# alarmclock4.net
KiCad netlist of a schematic drawn in EAGLE
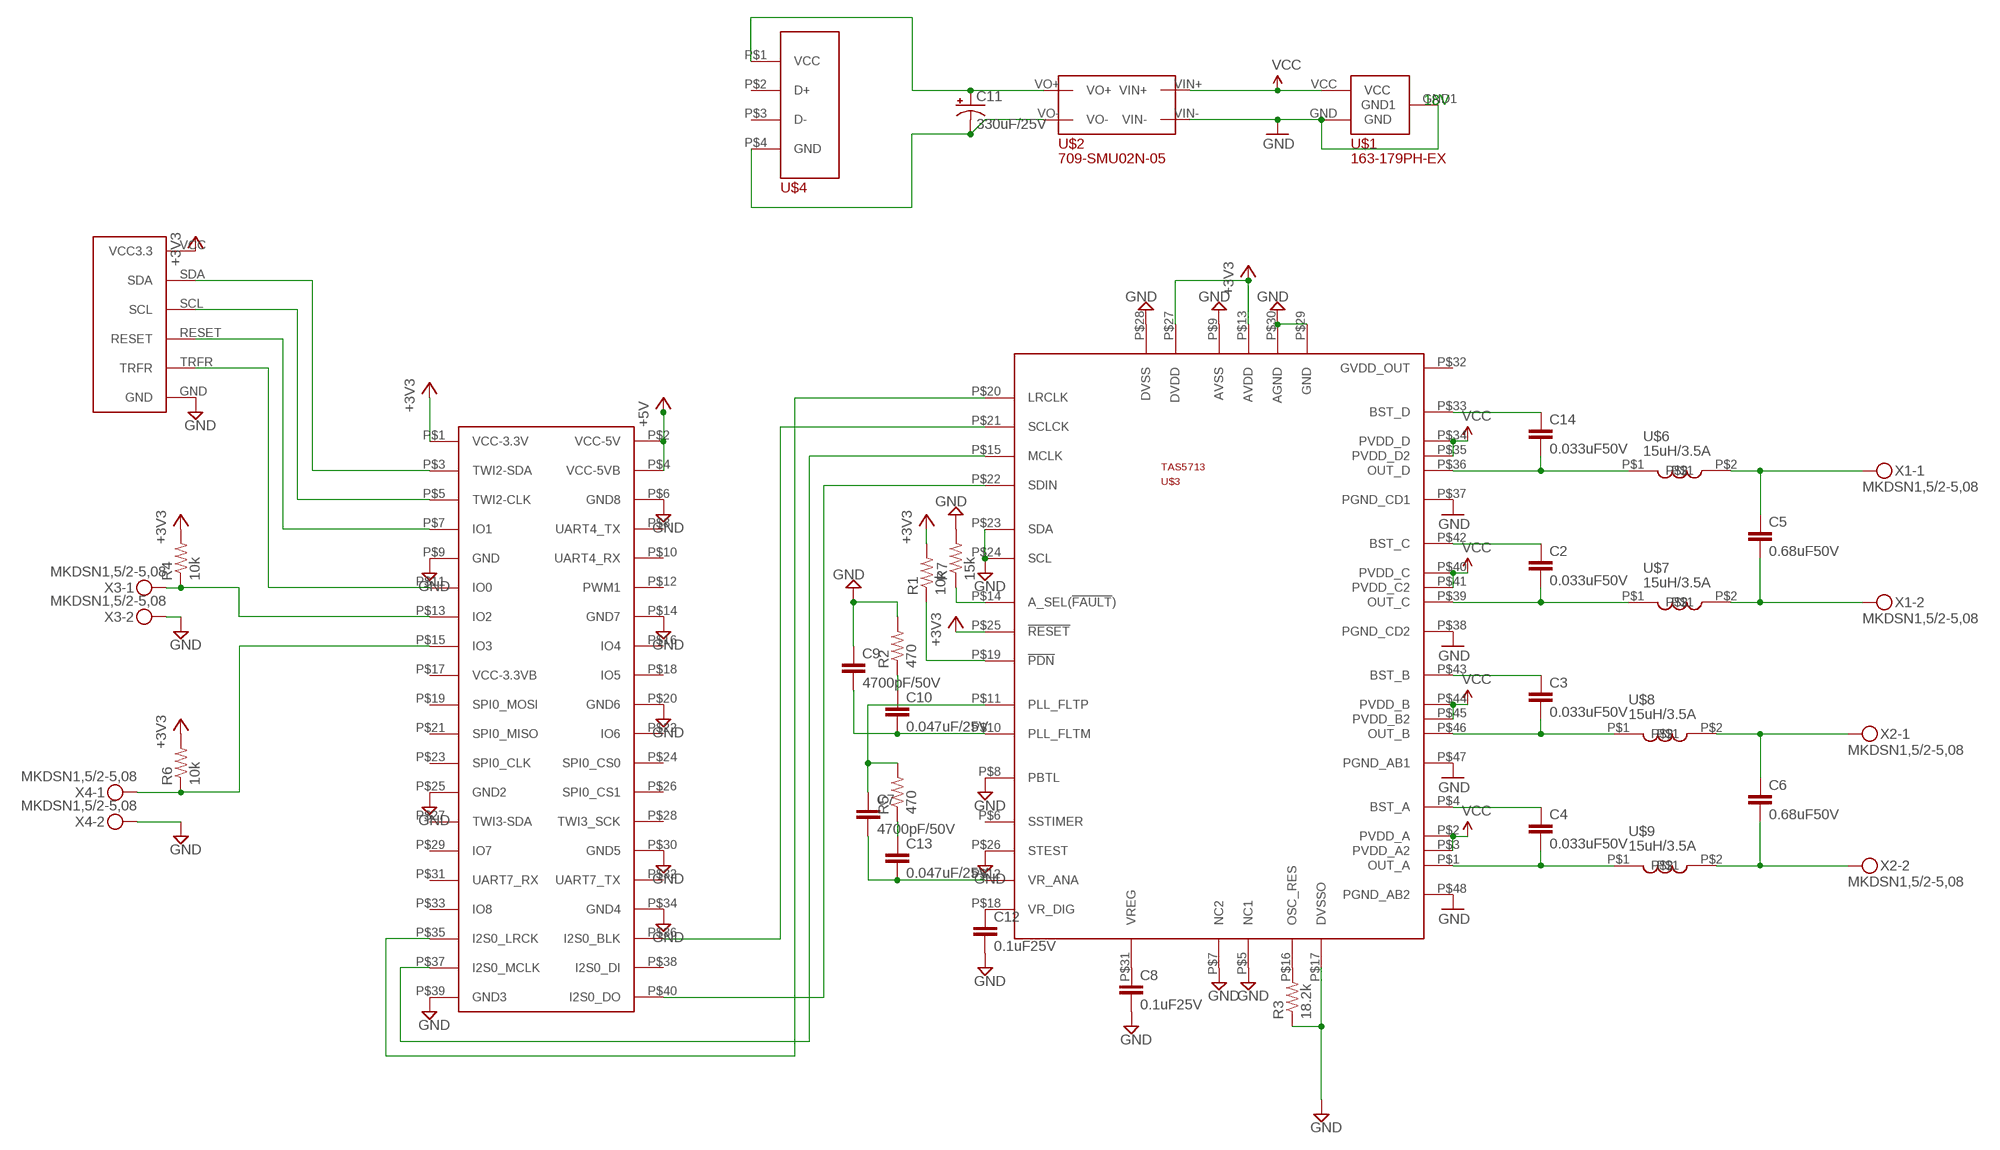
[diagram p0: schematic, sheet 1]

(export (version "E")
  (design (tool "Eeschema 10.0.6"))
  (components
    (comp (ref "C2")
      (value "0.033uF50V")
      (footprint "eagle-import:0603-CAP")
      (libsource (lib "eagle-import") (part "CAP0603-CAP"))
    )
    (comp (ref "C3")
      (value "0.033uF50V")
      (footprint "eagle-import:0603-CAP")
      (libsource (lib "eagle-import") (part "CAP0603-CAP"))
    )
    (comp (ref "C4")
      (value "0.033uF50V")
      (footprint "eagle-import:0603-CAP")
      (libsource (lib "eagle-import") (part "CAP0603-CAP"))
    )
    (comp (ref "C5")
      (value "0.68uF50V")
      (footprint "eagle-import:0603-CAP")
      (libsource (lib "eagle-import") (part "CAP0603-CAP"))
    )
    (comp (ref "C6")
      (value "0.68uF50V")
      (footprint "eagle-import:0603-CAP")
      (libsource (lib "eagle-import") (part "CAP0603-CAP"))
    )
    (comp (ref "C7")
      (value "4700pF/50V")
      (footprint "eagle-import:0603-CAP")
      (libsource (lib "eagle-import") (part "CAP0603-CAP"))
    )
    (comp (ref "C8")
      (value "0.1uF25V")
      (footprint "eagle-import:0603-CAP")
      (libsource (lib "eagle-import") (part "CAP0603-CAP"))
    )
    (comp (ref "C9")
      (value "4700pF/50V")
      (footprint "eagle-import:0603-CAP")
      (libsource (lib "eagle-import") (part "CAP0603-CAP"))
    )
    (comp (ref "C10")
      (value "0.047uF/25V")
      (footprint "eagle-import:0603-CAP")
      (libsource (lib "eagle-import") (part "CAP0603-CAP"))
    )
    (comp (ref "C11")
      (value "330uF/25V")
      (footprint "eagle-import:CPOL-RADIAL-10UF-25V")
      (libsource (lib "eagle-import") (part "CAP_POLPTH2"))
    )
    (comp (ref "C12")
      (value "0.1uF25V")
      (footprint "eagle-import:0603-CAP")
      (libsource (lib "eagle-import") (part "CAP0603-CAP"))
    )
    (comp (ref "C13")
      (value "0.047uF/25V")
      (footprint "eagle-import:0603-CAP")
      (libsource (lib "eagle-import") (part "CAP0603-CAP"))
    )
    (comp (ref "C14")
      (value "0.033uF50V")
      (footprint "eagle-import:0603-CAP")
      (libsource (lib "eagle-import") (part "CAP0603-CAP"))
    )
    (comp (ref "R1")
      (value "10k")
      (footprint "eagle-import:0603-RES")
      (libsource (lib "eagle-import") (part "RESISTOR0603-RES"))
    )
    (comp (ref "R2")
      (value "470")
      (footprint "eagle-import:0603-RES")
      (libsource (lib "eagle-import") (part "RESISTOR0603-RES"))
    )
    (comp (ref "R3")
      (value "18.2k")
      (footprint "eagle-import:0603-RES")
      (libsource (lib "eagle-import") (part "RESISTOR0603-RES"))
    )
    (comp (ref "R4")
      (value "10k")
      (footprint "eagle-import:0603-RES")
      (libsource (lib "eagle-import") (part "RESISTOR0603-RES"))
    )
    (comp (ref "R5")
      (value "470")
      (footprint "eagle-import:0603-RES")
      (libsource (lib "eagle-import") (part "RESISTOR0603-RES"))
    )
    (comp (ref "R6")
      (value "10k")
      (footprint "eagle-import:0603-RES")
      (libsource (lib "eagle-import") (part "RESISTOR0603-RES"))
    )
    (comp (ref "R7")
      (value "15k")
      (footprint "eagle-import:0603-RES")
      (libsource (lib "eagle-import") (part "RESISTOR0603-RES"))
    )
    (comp (ref "U$1")
      (value "163-179PH-EX")
      (footprint "eagle-import:163-179PH-EX_DIM")
      (libsource (lib "eagle-import") (part "163-179PH-EX"))
    )
    (comp (ref "U$2")
      (value "709-SMU02N-05")
      (footprint "eagle-import:709-SMU02N-05_DIM")
      (libsource (lib "eagle-import") (part "709-SMU02N-05"))
    )
    (comp (ref "U$3")
      (value "TAS5713")
      (footprint "eagle-import:TAS5713_DIM")
      (libsource (lib "eagle-import") (part "TAS5713"))
    )
    (comp (ref "U$4")
      (value "USB_TYPEA_CONNECTOR")
      (footprint "eagle-import:USB_DIM")
      (libsource (lib "eagle-import") (part "USB_TYPEA_CONNECTOR"))
    )
    (comp (ref "U$5")
      (value "BANANAPRO-CON6")
      (footprint "eagle-import:BANANAPRO-CON6_DIM")
      (libsource (lib "eagle-import") (part "BANANAPRO-CON6"))
    )
    (comp (ref "U$6")
      (value "15uH/3.5A")
      (footprint "eagle-import:MSS1260_DIM")
      (libsource (lib "eagle-import") (part "MSS1260INDUCTOR"))
    )
    (comp (ref "U$7")
      (value "15uH/3.5A")
      (footprint "eagle-import:MSS1260_DIM")
      (libsource (lib "eagle-import") (part "MSS1260INDUCTOR"))
    )
    (comp (ref "U$8")
      (value "15uH/3.5A")
      (footprint "eagle-import:MSS1260_DIM")
      (libsource (lib "eagle-import") (part "MSS1260INDUCTOR"))
    )
    (comp (ref "U$9")
      (value "15uH/3.5A")
      (footprint "eagle-import:MSS1260_DIM")
      (libsource (lib "eagle-import") (part "MSS1260INDUCTOR"))
    )
    (comp (ref "U$10")
      (value "SKYWRITER")
      (footprint "eagle-import:SKYWRITER_DIM")
      (libsource (lib "eagle-import") (part "SKYWRITER"))
    )
    (comp (ref "X1")
      (value "MKDSN1,5/2-5,08")
      (footprint "eagle-import:MKDSN1,5_2-5,08")
      (libsource (lib "eagle-import") (part "MKDSN1,5/2-5,08"))
    )
    (comp (ref "X2")
      (value "MKDSN1,5/2-5,08")
      (footprint "eagle-import:MKDSN1,5_2-5,08")
      (libsource (lib "eagle-import") (part "MKDSN1,5/2-5,08"))
    )
    (comp (ref "X3")
      (value "MKDSN1,5/2-5,08")
      (footprint "eagle-import:MKDSN1,5_2-5,08")
      (libsource (lib "eagle-import") (part "MKDSN1,5/2-5,08"))
    )
    (comp (ref "X4")
      (value "MKDSN1,5/2-5,08")
      (footprint "eagle-import:MKDSN1,5_2-5,08")
      (libsource (lib "eagle-import") (part "MKDSN1,5/2-5,08"))
    )
  )
  (nets
    (net (code "1") (name "+3V3") (class "Default")
      (node (ref "R1") (pin "2") (pinfunction "2_2") (pintype "passive"))
      (node (ref "R4") (pin "2") (pinfunction "2_2") (pintype "passive"))
      (node (ref "R6") (pin "2") (pinfunction "2_2") (pintype "passive"))
      (node (ref "U$10") (pin "VCC") (pinfunction "VCC3.3_VCC") (pintype "bidirectional"))
      (node (ref "U$3") (pin "P$13") (pinfunction "AVDD_P$13") (pintype "bidirectional"))
      (node (ref "U$3") (pin "P$25") (pinfunction "~{RESET}_P$25") (pintype "bidirectional"))
      (node (ref "U$3") (pin "P$27") (pinfunction "DVDD_P$27") (pintype "bidirectional"))
      (node (ref "U$5") (pin "P$1") (pinfunction "VCC-3.3V_P$1") (pintype "bidirectional"))
    )
    (net (code "2") (name "+5V") (class "Default")
      (node (ref "U$5") (pin "P$2") (pinfunction "VCC-5V_P$2") (pintype "bidirectional"))
      (node (ref "U$5") (pin "P$4") (pinfunction "VCC-5VB_P$4") (pintype "bidirectional"))
    )
    (net (code "3") (name "GND") (class "Default")
      (node (ref "C12") (pin "2") (pinfunction "2_2") (pintype "passive"))
      (node (ref "C8") (pin "2") (pinfunction "2_2") (pintype "passive"))
      (node (ref "C9") (pin "1") (pinfunction "1_1") (pintype "passive"))
      (node (ref "R2") (pin "2") (pinfunction "2_2") (pintype "passive"))
      (node (ref "R3") (pin "1") (pinfunction "1_1") (pintype "passive"))
      (node (ref "R7") (pin "2") (pinfunction "2_2") (pintype "passive"))
      (node (ref "U$1") (pin "GND") (pinfunction "GND_GND") (pintype "bidirectional"))
      (node (ref "U$1") (pin "GND1") (pinfunction "GND1_GND1") (pintype "bidirectional"))
      (node (ref "U$10") (pin "GND") (pinfunction "GND_GND") (pintype "bidirectional"))
      (node (ref "U$2") (pin "VIN-") (pinfunction "VIN-_VIN-") (pintype "bidirectional"))
      (node (ref "U$3") (pin "P$17") (pinfunction "DVSSO_P$17") (pintype "bidirectional"))
      (node (ref "U$3") (pin "P$23") (pinfunction "SDA_P$23") (pintype "bidirectional"))
      (node (ref "U$3") (pin "P$24") (pinfunction "SCL_P$24") (pintype "bidirectional"))
      (node (ref "U$3") (pin "P$26") (pinfunction "STEST_P$26") (pintype "bidirectional"))
      (node (ref "U$3") (pin "P$28") (pinfunction "DVSS_P$28") (pintype "bidirectional"))
      (node (ref "U$3") (pin "P$29") (pinfunction "GND_P$29") (pintype "bidirectional"))
      (node (ref "U$3") (pin "P$30") (pinfunction "AGND_P$30") (pintype "bidirectional"))
      (node (ref "U$3") (pin "P$37") (pinfunction "PGND_CD1_P$37") (pintype "bidirectional"))
      (node (ref "U$3") (pin "P$38") (pinfunction "PGND_CD2_P$38") (pintype "bidirectional"))
      (node (ref "U$3") (pin "P$47") (pinfunction "PGND_AB1_P$47") (pintype "bidirectional"))
      (node (ref "U$3") (pin "P$48") (pinfunction "PGND_AB2_P$48") (pintype "bidirectional"))
      (node (ref "U$3") (pin "P$5") (pinfunction "NC1_P$5") (pintype "bidirectional"))
      (node (ref "U$3") (pin "P$7") (pinfunction "NC2_P$7") (pintype "bidirectional"))
      (node (ref "U$3") (pin "P$8") (pinfunction "PBTL_P$8") (pintype "bidirectional"))
      (node (ref "U$3") (pin "P$9") (pinfunction "AVSS_P$9") (pintype "bidirectional"))
      (node (ref "U$5") (pin "P$14") (pinfunction "GND7_P$14") (pintype "bidirectional"))
      (node (ref "U$5") (pin "P$20") (pinfunction "GND6_P$20") (pintype "bidirectional"))
      (node (ref "U$5") (pin "P$25") (pinfunction "GND2_P$25") (pintype "bidirectional"))
      (node (ref "U$5") (pin "P$30") (pinfunction "GND5_P$30") (pintype "bidirectional"))
      (node (ref "U$5") (pin "P$34") (pinfunction "GND4_P$34") (pintype "bidirectional"))
      (node (ref "U$5") (pin "P$39") (pinfunction "GND3_P$39") (pintype "bidirectional"))
      (node (ref "U$5") (pin "P$6") (pinfunction "GND8_P$6") (pintype "bidirectional"))
      (node (ref "U$5") (pin "P$9") (pinfunction "GND_P$9") (pintype "bidirectional"))
      (node (ref "X3") (pin "2") (pinfunction "KL_2") (pintype "passive"))
      (node (ref "X4") (pin "2") (pinfunction "KL_2") (pintype "passive"))
    )
    (net (code "4") (name "Net-(C10-Pad1)") (class "Default")
      (node (ref "C10") (pin "1") (pinfunction "1_1") (pintype "passive"))
      (node (ref "R2") (pin "1") (pinfunction "1_1") (pintype "passive"))
    )
    (net (code "5") (name "Net-(C11-+)") (class "Default")
      (node (ref "C11") (pin "1") (pinfunction "+_1") (pintype "passive"))
      (node (ref "U$2") (pin "VO+") (pinfunction "VO+_VO+") (pintype "bidirectional"))
      (node (ref "U$4") (pin "P$1") (pinfunction "VCC_P$1") (pintype "bidirectional"))
    )
    (net (code "6") (name "Net-(C11--)") (class "Default")
      (node (ref "C11") (pin "2") (pinfunction "-_2") (pintype "passive"))
      (node (ref "U$2") (pin "VO-") (pinfunction "VO-_VO-") (pintype "bidirectional"))
      (node (ref "U$4") (pin "P$4") (pinfunction "GND_P$4") (pintype "bidirectional"))
    )
    (net (code "7") (name "Net-(C13-Pad1)") (class "Default")
      (node (ref "C13") (pin "1") (pinfunction "1_1") (pintype "passive"))
      (node (ref "R5") (pin "1") (pinfunction "1_1") (pintype "passive"))
    )
    (net (code "8") (name "Net-(U$3-A_SEL(~{FAULT}))") (class "Default")
      (node (ref "R7") (pin "1") (pinfunction "1_1") (pintype "passive"))
      (node (ref "U$3") (pin "P$14") (pinfunction "A_SEL(~{FAULT})_P$14") (pintype "bidirectional"))
    )
    (net (code "9") (name "Net-(U$3-BST_A)") (class "Default")
      (node (ref "C4") (pin "1") (pinfunction "1_1") (pintype "passive"))
      (node (ref "U$3") (pin "P$4") (pinfunction "BST_A_P$4") (pintype "bidirectional"))
    )
    (net (code "10") (name "Net-(U$3-BST_B)") (class "Default")
      (node (ref "C3") (pin "1") (pinfunction "1_1") (pintype "passive"))
      (node (ref "U$3") (pin "P$43") (pinfunction "BST_B_P$43") (pintype "bidirectional"))
    )
    (net (code "11") (name "Net-(U$3-BST_C)") (class "Default")
      (node (ref "C2") (pin "1") (pinfunction "1_1") (pintype "passive"))
      (node (ref "U$3") (pin "P$42") (pinfunction "BST_C_P$42") (pintype "bidirectional"))
    )
    (net (code "12") (name "Net-(U$3-BST_D)") (class "Default")
      (node (ref "C14") (pin "1") (pinfunction "1_1") (pintype "passive"))
      (node (ref "U$3") (pin "P$33") (pinfunction "BST_D_P$33") (pintype "bidirectional"))
    )
    (net (code "13") (name "Net-(U$3-LRCLK)") (class "Default")
      (node (ref "U$3") (pin "P$20") (pinfunction "LRCLK_P$20") (pintype "bidirectional"))
      (node (ref "U$5") (pin "P$35") (pinfunction "I2S0_LRCK_P$35") (pintype "bidirectional"))
    )
    (net (code "14") (name "Net-(U$3-MCLK)") (class "Default")
      (node (ref "U$3") (pin "P$15") (pinfunction "MCLK_P$15") (pintype "bidirectional"))
      (node (ref "U$5") (pin "P$37") (pinfunction "I2S0_MCLK_P$37") (pintype "bidirectional"))
    )
    (net (code "15") (name "Net-(U$3-OSC_RES)") (class "Default")
      (node (ref "R3") (pin "2") (pinfunction "2_2") (pintype "passive"))
      (node (ref "U$3") (pin "P$16") (pinfunction "OSC_RES_P$16") (pintype "bidirectional"))
    )
    (net (code "16") (name "Net-(U$3-OUT_A)") (class "Default")
      (node (ref "C4") (pin "2") (pinfunction "2_2") (pintype "passive"))
      (node (ref "U$3") (pin "P$1") (pinfunction "OUT_A_P$1") (pintype "bidirectional"))
      (node (ref "U$9") (pin "P$1") (pinfunction "P$1_P$1") (pintype "bidirectional"))
    )
    (net (code "17") (name "Net-(U$3-OUT_B)") (class "Default")
      (node (ref "C3") (pin "2") (pinfunction "2_2") (pintype "passive"))
      (node (ref "U$3") (pin "P$46") (pinfunction "OUT_B_P$46") (pintype "bidirectional"))
      (node (ref "U$8") (pin "P$1") (pinfunction "P$1_P$1") (pintype "bidirectional"))
    )
    (net (code "18") (name "Net-(U$3-OUT_C)") (class "Default")
      (node (ref "C2") (pin "2") (pinfunction "2_2") (pintype "passive"))
      (node (ref "U$3") (pin "P$39") (pinfunction "OUT_C_P$39") (pintype "bidirectional"))
      (node (ref "U$7") (pin "P$1") (pinfunction "P$1_P$1") (pintype "bidirectional"))
    )
    (net (code "19") (name "Net-(U$3-OUT_D)") (class "Default")
      (node (ref "C14") (pin "2") (pinfunction "2_2") (pintype "passive"))
      (node (ref "U$3") (pin "P$36") (pinfunction "OUT_D_P$36") (pintype "bidirectional"))
      (node (ref "U$6") (pin "P$1") (pinfunction "P$1_P$1") (pintype "bidirectional"))
    )
    (net (code "20") (name "Net-(U$3-PLL_FLTM)") (class "Default")
      (node (ref "C10") (pin "2") (pinfunction "2_2") (pintype "passive"))
      (node (ref "C9") (pin "2") (pinfunction "2_2") (pintype "passive"))
      (node (ref "U$3") (pin "P$10") (pinfunction "PLL_FLTM_P$10") (pintype "bidirectional"))
    )
    (net (code "21") (name "Net-(U$3-PLL_FLTP)") (class "Default")
      (node (ref "C7") (pin "1") (pinfunction "1_1") (pintype "passive"))
      (node (ref "R5") (pin "2") (pinfunction "2_2") (pintype "passive"))
      (node (ref "U$3") (pin "P$11") (pinfunction "PLL_FLTP_P$11") (pintype "bidirectional"))
    )
    (net (code "22") (name "Net-(U$3-SCLCK)") (class "Default")
      (node (ref "U$3") (pin "P$21") (pinfunction "SCLCK_P$21") (pintype "bidirectional"))
      (node (ref "U$5") (pin "P$36") (pinfunction "I2S0_BLK_P$36") (pintype "bidirectional"))
    )
    (net (code "23") (name "Net-(U$3-SDIN)") (class "Default")
      (node (ref "U$3") (pin "P$22") (pinfunction "SDIN_P$22") (pintype "bidirectional"))
      (node (ref "U$5") (pin "P$40") (pinfunction "I2S0_DO_P$40") (pintype "bidirectional"))
    )
    (net (code "24") (name "Net-(U$3-VREG)") (class "Default")
      (node (ref "C8") (pin "1") (pinfunction "1_1") (pintype "passive"))
      (node (ref "U$3") (pin "P$31") (pinfunction "VREG_P$31") (pintype "bidirectional"))
    )
    (net (code "25") (name "Net-(U$3-VR_ANA)") (class "Default")
      (node (ref "C13") (pin "2") (pinfunction "2_2") (pintype "passive"))
      (node (ref "C7") (pin "2") (pinfunction "2_2") (pintype "passive"))
      (node (ref "U$3") (pin "P$12") (pinfunction "VR_ANA_P$12") (pintype "bidirectional"))
    )
    (net (code "26") (name "Net-(U$3-VR_DIG)") (class "Default")
      (node (ref "C12") (pin "1") (pinfunction "1_1") (pintype "passive"))
      (node (ref "U$3") (pin "P$18") (pinfunction "VR_DIG_P$18") (pintype "bidirectional"))
    )
    (net (code "27") (name "Net-(U$3-~{PDN})") (class "Default")
      (node (ref "R1") (pin "1") (pinfunction "1_1") (pintype "passive"))
      (node (ref "U$3") (pin "P$19") (pinfunction "~{PDN}_P$19") (pintype "bidirectional"))
    )
    (net (code "28") (name "Net-(U$5-IO0)") (class "Default")
      (node (ref "U$10") (pin "TRFR") (pinfunction "TRFR_TRFR") (pintype "bidirectional"))
      (node (ref "U$5") (pin "P$11") (pinfunction "IO0_P$11") (pintype "bidirectional"))
    )
    (net (code "29") (name "Net-(U$5-IO1)") (class "Default")
      (node (ref "U$10") (pin "RESET") (pinfunction "RESET_RESET") (pintype "bidirectional"))
      (node (ref "U$5") (pin "P$7") (pinfunction "IO1_P$7") (pintype "bidirectional"))
    )
    (net (code "30") (name "Net-(U$5-IO2)") (class "Default")
      (node (ref "R4") (pin "1") (pinfunction "1_1") (pintype "passive"))
      (node (ref "U$5") (pin "P$13") (pinfunction "IO2_P$13") (pintype "bidirectional"))
      (node (ref "X3") (pin "1") (pinfunction "KL_1") (pintype "passive"))
    )
    (net (code "31") (name "Net-(U$5-IO3)") (class "Default")
      (node (ref "R6") (pin "1") (pinfunction "1_1") (pintype "passive"))
      (node (ref "U$5") (pin "P$15") (pinfunction "IO3_P$15") (pintype "bidirectional"))
      (node (ref "X4") (pin "1") (pinfunction "KL_1") (pintype "passive"))
    )
    (net (code "32") (name "Net-(U$5-TWI2-CLK)") (class "Default")
      (node (ref "U$10") (pin "SCL") (pinfunction "SCL_SCL") (pintype "bidirectional"))
      (node (ref "U$5") (pin "P$5") (pinfunction "TWI2-CLK_P$5") (pintype "bidirectional"))
    )
    (net (code "33") (name "Net-(U$5-TWI2-SDA)") (class "Default")
      (node (ref "U$10") (pin "SDA") (pinfunction "SDA_SDA") (pintype "bidirectional"))
      (node (ref "U$5") (pin "P$3") (pinfunction "TWI2-SDA_P$3") (pintype "bidirectional"))
    )
    (net (code "34") (name "Net-(X1A-KL)") (class "Default")
      (node (ref "C5") (pin "1") (pinfunction "1_1") (pintype "passive"))
      (node (ref "U$6") (pin "P$2") (pinfunction "P$2_P$2") (pintype "bidirectional"))
      (node (ref "X1") (pin "1") (pinfunction "KL_1") (pintype "passive"))
    )
    (net (code "35") (name "Net-(X1B-KL)") (class "Default")
      (node (ref "C5") (pin "2") (pinfunction "2_2") (pintype "passive"))
      (node (ref "U$7") (pin "P$2") (pinfunction "P$2_P$2") (pintype "bidirectional"))
      (node (ref "X1") (pin "2") (pinfunction "KL_2") (pintype "passive"))
    )
    (net (code "36") (name "Net-(X2A-KL)") (class "Default")
      (node (ref "C6") (pin "1") (pinfunction "1_1") (pintype "passive"))
      (node (ref "U$8") (pin "P$2") (pinfunction "P$2_P$2") (pintype "bidirectional"))
      (node (ref "X2") (pin "1") (pinfunction "KL_1") (pintype "passive"))
    )
    (net (code "37") (name "Net-(X2B-KL)") (class "Default")
      (node (ref "C6") (pin "2") (pinfunction "2_2") (pintype "passive"))
      (node (ref "U$9") (pin "P$2") (pinfunction "P$2_P$2") (pintype "bidirectional"))
      (node (ref "X2") (pin "2") (pinfunction "KL_2") (pintype "passive"))
    )
    (net (code "38") (name "VCC") (class "Default")
      (node (ref "U$1") (pin "VCC") (pinfunction "VCC_VCC") (pintype "bidirectional"))
      (node (ref "U$2") (pin "VIN+") (pinfunction "VIN+_VIN+") (pintype "bidirectional"))
      (node (ref "U$3") (pin "P$2") (pinfunction "PVDD_A_P$2") (pintype "bidirectional"))
      (node (ref "U$3") (pin "P$3") (pinfunction "PVDD_A2_P$3") (pintype "bidirectional"))
      (node (ref "U$3") (pin "P$34") (pinfunction "PVDD_D_P$34") (pintype "bidirectional"))
      (node (ref "U$3") (pin "P$35") (pinfunction "PVDD_D2_P$35") (pintype "bidirectional"))
      (node (ref "U$3") (pin "P$40") (pinfunction "PVDD_C_P$40") (pintype "bidirectional"))
      (node (ref "U$3") (pin "P$41") (pinfunction "PVDD_C2_P$41") (pintype "bidirectional"))
      (node (ref "U$3") (pin "P$44") (pinfunction "PVDD_B_P$44") (pintype "bidirectional"))
      (node (ref "U$3") (pin "P$45") (pinfunction "PVDD_B2_P$45") (pintype "bidirectional"))
    )
    (net (code "39") (name "unconnected-(U$3-GVDD_OUT-PadP$32)") (class "Default")
      (node (ref "U$3") (pin "P$32") (pinfunction "GVDD_OUT_P$32") (pintype "bidirectional"))
    )
    (net (code "40") (name "unconnected-(U$3-SSTIMER-PadP$6)") (class "Default")
      (node (ref "U$3") (pin "P$6") (pinfunction "SSTIMER_P$6") (pintype "bidirectional"))
    )
    (net (code "41") (name "unconnected-(U$4-D+-PadP$2)") (class "Default")
      (node (ref "U$4") (pin "P$2") (pinfunction "D+_P$2") (pintype "bidirectional"))
    )
    (net (code "42") (name "unconnected-(U$4-D--PadP$3)") (class "Default")
      (node (ref "U$4") (pin "P$3") (pinfunction "D-_P$3") (pintype "bidirectional"))
    )
    (net (code "43") (name "unconnected-(U$5-I2S0_DI-PadP$38)") (class "Default")
      (node (ref "U$5") (pin "P$38") (pinfunction "I2S0_DI_P$38") (pintype "bidirectional"))
    )
    (net (code "44") (name "unconnected-(U$5-IO4-PadP$16)") (class "Default")
      (node (ref "U$5") (pin "P$16") (pinfunction "IO4_P$16") (pintype "bidirectional"))
    )
    (net (code "45") (name "unconnected-(U$5-IO5-PadP$18)") (class "Default")
      (node (ref "U$5") (pin "P$18") (pinfunction "IO5_P$18") (pintype "bidirectional"))
    )
    (net (code "46") (name "unconnected-(U$5-IO6-PadP$22)") (class "Default")
      (node (ref "U$5") (pin "P$22") (pinfunction "IO6_P$22") (pintype "bidirectional"))
    )
    (net (code "47") (name "unconnected-(U$5-IO7-PadP$29)") (class "Default")
      (node (ref "U$5") (pin "P$29") (pinfunction "IO7_P$29") (pintype "bidirectional"))
    )
    (net (code "48") (name "unconnected-(U$5-IO8-PadP$33)") (class "Default")
      (node (ref "U$5") (pin "P$33") (pinfunction "IO8_P$33") (pintype "bidirectional"))
    )
    (net (code "49") (name "unconnected-(U$5-PWM1-PadP$12)") (class "Default")
      (node (ref "U$5") (pin "P$12") (pinfunction "PWM1_P$12") (pintype "bidirectional"))
    )
    (net (code "50") (name "unconnected-(U$5-SPI0_CLK-PadP$23)") (class "Default")
      (node (ref "U$5") (pin "P$23") (pinfunction "SPI0_CLK_P$23") (pintype "bidirectional"))
    )
    (net (code "51") (name "unconnected-(U$5-SPI0_CS0-PadP$24)") (class "Default")
      (node (ref "U$5") (pin "P$24") (pinfunction "SPI0_CS0_P$24") (pintype "bidirectional"))
    )
    (net (code "52") (name "unconnected-(U$5-SPI0_CS1-PadP$26)") (class "Default")
      (node (ref "U$5") (pin "P$26") (pinfunction "SPI0_CS1_P$26") (pintype "bidirectional"))
    )
    (net (code "53") (name "unconnected-(U$5-SPI0_MISO-PadP$21)") (class "Default")
      (node (ref "U$5") (pin "P$21") (pinfunction "SPI0_MISO_P$21") (pintype "bidirectional"))
    )
    (net (code "54") (name "unconnected-(U$5-SPI0_MOSI-PadP$19)") (class "Default")
      (node (ref "U$5") (pin "P$19") (pinfunction "SPI0_MOSI_P$19") (pintype "bidirectional"))
    )
    (net (code "55") (name "unconnected-(U$5-TWI3-SDA-PadP$27)") (class "Default")
      (node (ref "U$5") (pin "P$27") (pinfunction "TWI3-SDA_P$27") (pintype "bidirectional"))
    )
    (net (code "56") (name "unconnected-(U$5-TWI3_SCK-PadP$28)") (class "Default")
      (node (ref "U$5") (pin "P$28") (pinfunction "TWI3_SCK_P$28") (pintype "bidirectional"))
    )
    (net (code "57") (name "unconnected-(U$5-UART4_RX-PadP$10)") (class "Default")
      (node (ref "U$5") (pin "P$10") (pinfunction "UART4_RX_P$10") (pintype "bidirectional"))
    )
    (net (code "58") (name "unconnected-(U$5-UART4_TX-PadP$8)") (class "Default")
      (node (ref "U$5") (pin "P$8") (pinfunction "UART4_TX_P$8") (pintype "bidirectional"))
    )
    (net (code "59") (name "unconnected-(U$5-UART7_RX-PadP$31)") (class "Default")
      (node (ref "U$5") (pin "P$31") (pinfunction "UART7_RX_P$31") (pintype "bidirectional"))
    )
    (net (code "60") (name "unconnected-(U$5-UART7_TX-PadP$32)") (class "Default")
      (node (ref "U$5") (pin "P$32") (pinfunction "UART7_TX_P$32") (pintype "bidirectional"))
    )
    (net (code "61") (name "unconnected-(U$5-VCC-3.3VB-PadP$17)") (class "Default")
      (node (ref "U$5") (pin "P$17") (pinfunction "VCC-3.3VB_P$17") (pintype "bidirectional"))
    )
  )
)
